# 1A19J4_1A20J1_A.net
KiCad netlist of a schematic drawn in Altium Designer
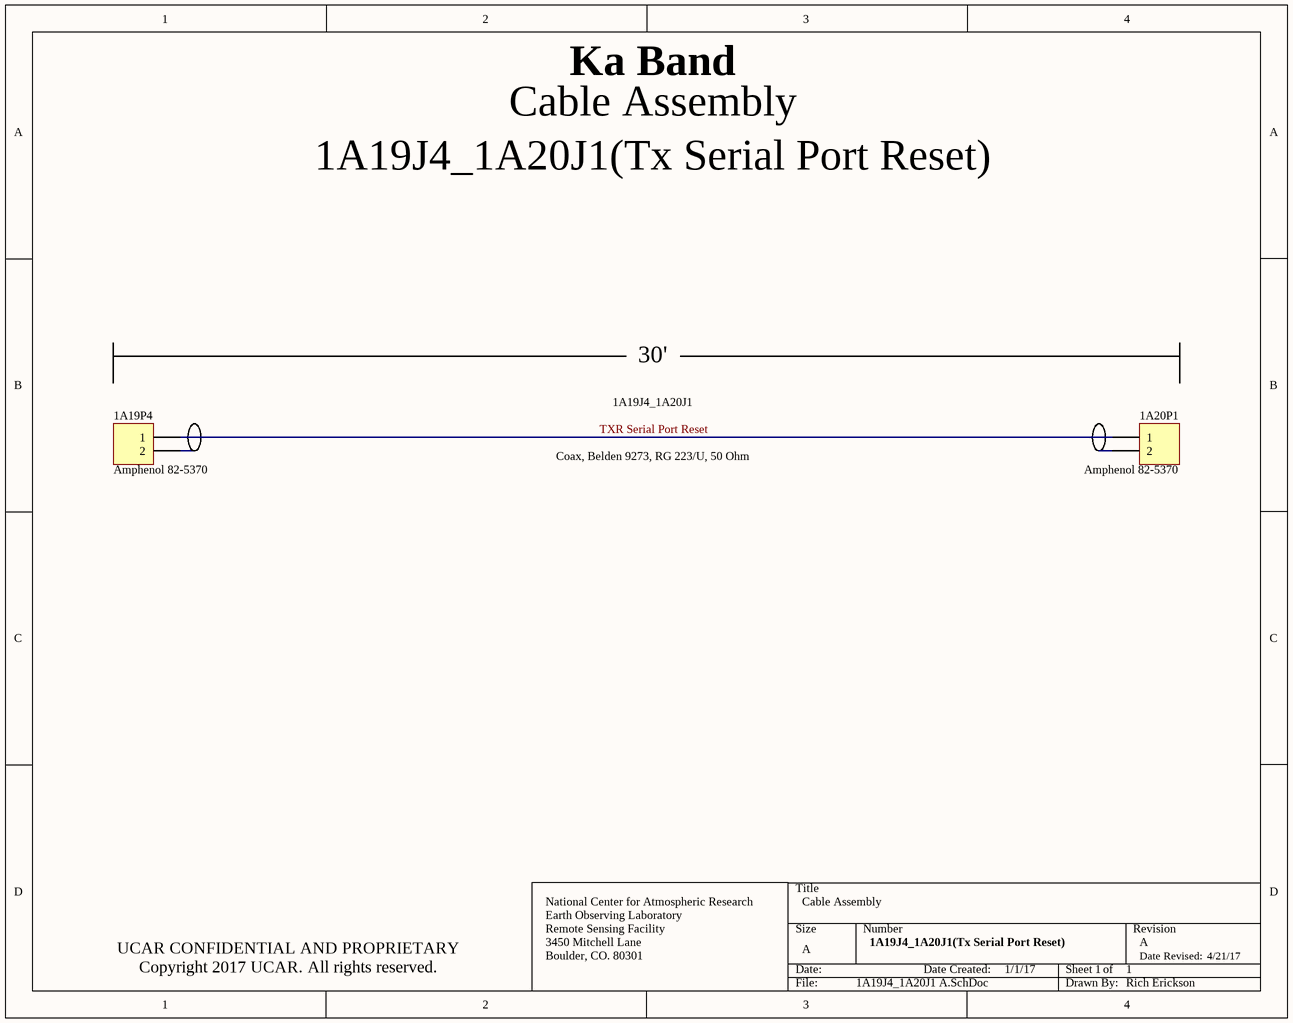
[diagram p0: 1A19J4_1A20J1 A.SchDoc]

(export (version "E")
  (design (tool "Eeschema 10.0.6"))
  (components
    (comp (ref "1A19P4")
      (value "Amphenol 82-5370")
      (footprint "HDR1X2")
      (description "Header, 2-Pin")
      (fields (field (name "PUBLISHER") "Altium Limited"))
      (libsource (lib "") (part "Header 2_1"))
    )
    (comp (ref "1A20P1")
      (value "Amphenol 82-5370")
      (footprint "HDR1X2")
      (description "Header, 2-Pin")
      (fields (field (name "PUBLISHER") "Altium Limited"))
      (libsource (lib "Miscellaneous Connectors") (part "Header 2"))
    )
  )
  (nets
    (net (code "1") (name "/TXR Serial Port Reset") (class "Default")
      (node (ref "1A19P4") (pin "1") (pinfunction "1_1") (pintype "passive"))
      (node (ref "1A20P1") (pin "1") (pinfunction "1_1") (pintype "passive"))
    )
    (net (code "2") (name "unconnected-(1A19P4-Pad2)") (class "Default")
      (node (ref "1A19P4") (pin "2") (pinfunction "2_2") (pintype "passive"))
    )
    (net (code "3") (name "unconnected-(1A20P1-Pad2)") (class "Default")
      (node (ref "1A20P1") (pin "2") (pinfunction "2_2") (pintype "passive"))
    )
  )
)
